# 01_POWER.net
KiCad netlist of a schematic drawn in Altium Designer
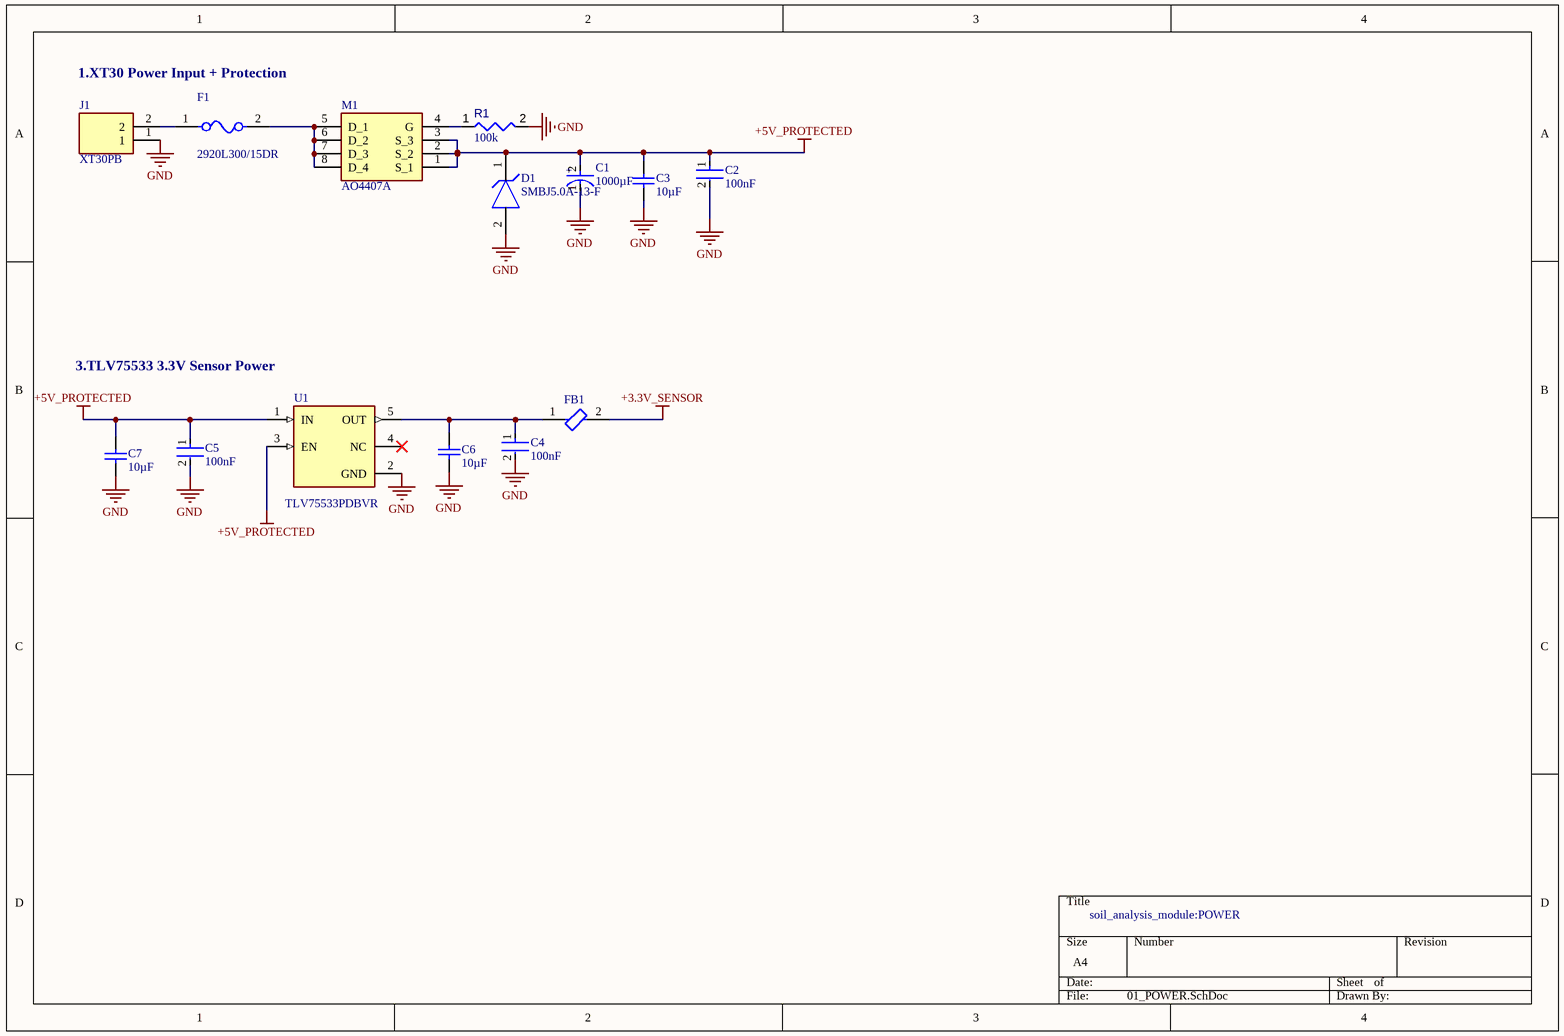
[diagram p0: 01_POWER.SchDoc]

(export (version "E")
  (design (tool "Eeschema 10.0.6"))
  (components
    (comp (ref "C1")
      (value "1000µF")
      (footprint "FP-RAD-TH-D_8_0_5-L_15_1-MFG")
      (description "Aluminum Electrolytic Capacitor, 1000 uF, 10 V, ± 20%, 8000 hours @ 105°C, Radial Leaded")
      (fields (field (name "TOLERANCE") "20%") (field (name "Comment") "EEUFR1A102L"))
      (libsource (lib "Maksym Pleshyvtsev") (part "a00bbbee19879c290e62620ae7e47b1"))
    )
    (comp (ref "C2")
      (value "100nF")
      (footprint "FP-CC1206-1_25-MFG")
      (description "50V 100nF X7R ±10% 1206 Multilayer Ceramic Capacitors MLCC - SMD/SMT ROHS")
      (fields (field (name "TOLERANCE") "10%") (field (name "Comment") "CC1206KRX7R9BB104"))
      (libsource (lib "Maksym Pleshyvtsev") (part "11868f565c42a9108669ba33697ecf6"))
    )
    (comp (ref "C3")
      (value "10µF")
      (footprint "CAPC3216X180X55ML20T25")
      (description "16V 10uF X7R ±10% 1206 Multilayer Ceramic Capacitors MLCC - SMD/SMT ROHS")
      (fields (field (name "TOLERANCE") "10%") (field (name "Comment") "GRM31CR71C106KA12L"))
      (libsource (lib "Maksym Pleshyvtsev") (part "CAP-NP-2"))
    )
    (comp (ref "C4")
      (value "100nF")
      (footprint "FP-CC1206-1_25-MFG")
      (description "50V 100nF X7R ±10% 1206 Multilayer Ceramic Capacitors MLCC - SMD/SMT ROHS")
      (fields (field (name "TOLERANCE") "10%") (field (name "Comment") "CC1206KRX7R9BB104"))
      (libsource (lib "Maksym Pleshyvtsev") (part "11868f565c42a9108669ba33697ecf6"))
    )
    (comp (ref "C5")
      (value "100nF")
      (footprint "FP-CC1206-1_25-MFG")
      (description "50V 100nF X7R ±10% 1206 Multilayer Ceramic Capacitors MLCC - SMD/SMT ROHS")
      (fields (field (name "TOLERANCE") "10%") (field (name "Comment") "CC1206KRX7R9BB104"))
      (libsource (lib "Maksym Pleshyvtsev") (part "11868f565c42a9108669ba33697ecf6"))
    )
    (comp (ref "C6")
      (value "10µF")
      (footprint "CAPC3216X180X55ML20T25")
      (description "16V 10uF X7R ±10% 1206 Multilayer Ceramic Capacitors MLCC - SMD/SMT ROHS")
      (fields (field (name "TOLERANCE") "10%") (field (name "Comment") "GRM31CR71C106KA12L"))
      (libsource (lib "Maksym Pleshyvtsev") (part "CAP-NP-2"))
    )
    (comp (ref "C7")
      (value "10µF")
      (footprint "CAPC3216X180X55ML20T25")
      (description "16V 10uF X7R ±10% 1206 Multilayer Ceramic Capacitors MLCC - SMD/SMT ROHS")
      (fields (field (name "TOLERANCE") "10%") (field (name "Comment") "GRM31CR71C106KA12L"))
      (libsource (lib "Maksym Pleshyvtsev") (part "CAP-NP-2"))
    )
    (comp (ref "D1")
      (value "SMBJ5.0A-13-F")
      (footprint "FP-SMB-MFG")
      (description "SMBJ5.0A Series 600 W 5.0 V Surface Mount Uni-Directional TVS Diode - DO-214AA")
      (libsource (lib "Maksym Pleshyvtsev") (part "673ecd2ea4d7fb87b4005b0cb348b7d"))
    )
    (comp (ref "F1")
      (value "2920L300/15DR")
      (footprint "FP-2920L-MFG")
      (description "PTC Resettable Fuses; 2920L300/15DR; LITTELFUSE; 5 A; 3 A; 20 s; 2920")
      (libsource (lib "Maksym Pleshyvtsev") (part "5bcf9b9f640e542cf0359d10258e979"))
    )
    (comp (ref "FB1")
      (value "BLM31PG121SN1L")
      (footprint "FP-BLM31-0_2-t1_1-MFG")
      (description "Ferrite Beads Multi-Layer 120Ohm 25% 100MHz 3.5A 0.02Ohm DCR 1206 T/R")
      (fields (field (name "TOLERANCE") "25%"))
      (libsource (lib "Maksym Pleshyvtsev") (part "5f30dd21d616792df468990f7003faa"))
    )
    (comp (ref "J1")
      (value "XT30PB")
      (footprint "XT30PB-Footprint-1")
      (description "Mini XT60 XT30 Connector for RC Multirotor Racing Drone Quadcopter")
      (libsource (lib "Maksym Pleshyvtsev") (part "XT30PB-Symbol-1"))
    )
    (comp (ref "M1")
      (value "AO4407A")
      (footprint "AO4407A-Footprint-1")
      (description "Mosfet P-ch 30V 12A 8SOIC / Trans Mosfet P-ch 30V 12A 8-PIN SOIC")
      (libsource (lib "Maksym Pleshyvtsev") (part "AO4407A-Symbol-1"))
    )
    (comp (ref "R1")
      (value "100k")
      (footprint "RESC3216X60X45ML15T20")
      (description "Chip Resistor, 100 KOhm, +/- 1%, 0.25 W, -55 to 155 degC, 1206 (3216 Metric)")
      (fields (field (name "TOLERANCE") "1%") (field (name "POWER") "250mW"))
      (libsource (lib "Maksym Pleshyvtsev") (part "RES-2"))
    )
    (comp (ref "U1")
      (value "TLV75533PDBVR")
      (footprint "FP-DBV0005A-MFG")
      (description "500mA high-PSRR low-IQ low-dropout voltage regulator with enable 5-SOT-23 -40 to 125")
      (libsource (lib "Maksym Pleshyvtsev") (part "bc27d4aa6bca38f00d7b0ca125c90e0"))
    )
  )
  (nets
    (net (code "1") (name "+3.3V_SENSOR") (class "Default")
      (node (ref "FB1") (pin "2") (pinfunction "2_2") (pintype "passive"))
    )
    (net (code "2") (name "+5V_PROTECTED") (class "Default")
      (node (ref "C1") (pin "2") (pinfunction "A_2") (pintype "passive"))
      (node (ref "C2") (pin "1") (pinfunction "1_1") (pintype "passive"))
      (node (ref "C3") (pin "2") (pinfunction "2_2") (pintype "passive"))
      (node (ref "C5") (pin "1") (pinfunction "1_1") (pintype "passive"))
      (node (ref "C7") (pin "2") (pinfunction "2_2") (pintype "passive"))
      (node (ref "D1") (pin "1") (pinfunction "C_1") (pintype "passive"))
      (node (ref "M1") (pin "1") (pinfunction "S_1_1") (pintype "passive"))
      (node (ref "M1") (pin "2") (pinfunction "S_2_2") (pintype "passive"))
      (node (ref "M1") (pin "3") (pinfunction "S_3_3") (pintype "passive"))
      (node (ref "U1") (pin "1") (pinfunction "IN_1") (pintype "input"))
      (node (ref "U1") (pin "3") (pinfunction "EN_3") (pintype "input"))
    )
    (net (code "3") (name "GND") (class "Default")
      (node (ref "C1") (pin "1") (pinfunction "C_1") (pintype "passive"))
      (node (ref "C2") (pin "2") (pinfunction "2_2") (pintype "passive"))
      (node (ref "C3") (pin "1") (pinfunction "1_1") (pintype "passive"))
      (node (ref "C4") (pin "2") (pinfunction "2_2") (pintype "passive"))
      (node (ref "C5") (pin "2") (pinfunction "2_2") (pintype "passive"))
      (node (ref "C6") (pin "1") (pinfunction "1_1") (pintype "passive"))
      (node (ref "C7") (pin "1") (pinfunction "1_1") (pintype "passive"))
      (node (ref "D1") (pin "2") (pinfunction "A_2") (pintype "passive"))
      (node (ref "J1") (pin "1") (pinfunction "1_1") (pintype "passive"))
      (node (ref "R1") (pin "2") (pinfunction "2_2") (pintype "passive"))
      (node (ref "U1") (pin "2") (pinfunction "GND_2") (pintype "power_in"))
    )
    (net (code "4") (name "Net-(F1-Pad1)") (class "Default")
      (node (ref "F1") (pin "1") (pinfunction "1_1") (pintype "passive"))
      (node (ref "J1") (pin "2") (pinfunction "2_2") (pintype "passive"))
    )
    (net (code "5") (name "Net-(M1-D_1)") (class "Default")
      (node (ref "F1") (pin "2") (pinfunction "2_2") (pintype "passive"))
      (node (ref "M1") (pin "5") (pinfunction "D_1_5") (pintype "passive"))
      (node (ref "M1") (pin "6") (pinfunction "D_2_6") (pintype "passive"))
      (node (ref "M1") (pin "7") (pinfunction "D_3_7") (pintype "passive"))
      (node (ref "M1") (pin "8") (pinfunction "D_4_8") (pintype "passive"))
    )
    (net (code "6") (name "Net-(M1-G)") (class "Default")
      (node (ref "M1") (pin "4") (pinfunction "G_4") (pintype "passive"))
      (node (ref "R1") (pin "1") (pinfunction "1_1") (pintype "passive"))
    )
    (net (code "7") (name "Net-(U1-OUT)") (class "Default")
      (node (ref "C4") (pin "1") (pinfunction "1_1") (pintype "passive"))
      (node (ref "C6") (pin "2") (pinfunction "2_2") (pintype "passive"))
      (node (ref "FB1") (pin "1") (pinfunction "1_1") (pintype "passive"))
      (node (ref "U1") (pin "5") (pinfunction "OUT_5") (pintype "output"))
    )
    (net (code "8") (name "unconnected-(U1-NC-Pad4)") (class "Default")
      (node (ref "U1") (pin "4") (pinfunction "NC_4") (pintype "passive+no_connect"))
    )
  )
)
